# CH340_USB_To_UART.net
KiCad netlist of a schematic drawn in Altium Designer
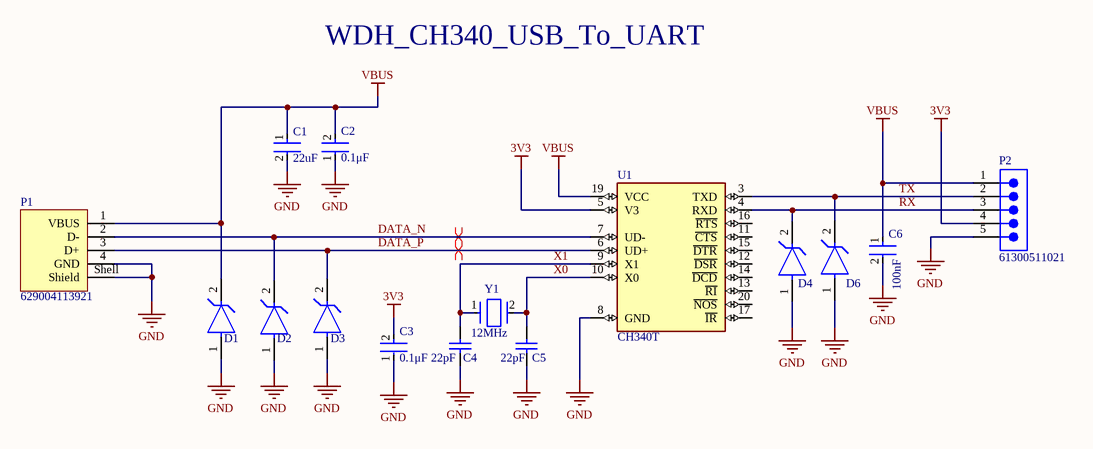
[diagram p0: CH340_USB_To_UART.SchDoc]

(export (version "E")
  (design (tool "Eeschema 10.0.6"))
  (components
    (comp (ref "C1")
      (value "22uF")
      (footprint "FP-CL05A226MQ5N6J8-IPC_C")
      (description "CAP CER 22UF 6.3V X5R 0402")
      (fields
        (field (name "MANUFACTURER PART NUMBER") "CL05A226MQ5N6J8")
        (field (name "MANUFACTURER") "Samsung Electro-Mechanics")
      )
      (libsource (lib "Altium Content Vault") (part "11868f565c42a9108669ba33697ecf6"))
    )
    (comp (ref "C2")
      (value "GRM155R71C104KA88D")
      (footprint "FP-GRM15-MFG")
      (description "CAP CER 0.1UF 16V X7R 0402")
      (fields
        (field (name "TOLERANCE") "10%")
        (field (name "OCTOPART") "https://octopart.com/grm155r71c104ka88d-murata-196880")
        (field (name "CAPACITANCE") "0.1μF")
      )
      (libsource (lib "Altium Content Vault") (part "236180d848d6139a670b325ea6854c9"))
    )
    (comp (ref "C3")
      (value "GRM155R71C104KA88D")
      (footprint "FP-GRM15-MFG")
      (description "CAP CER 0.1UF 16V X7R 0402")
      (fields
        (field (name "TOLERANCE") "10%")
        (field (name "OCTOPART") "https://octopart.com/grm155r71c104ka88d-murata-196880")
        (field (name "CAPACITANCE") "0.1μF")
      )
      (libsource (lib "Altium Content Vault") (part "236180d848d6139a670b325ea6854c9"))
    )
    (comp (ref "C4")
      (value "0402ZK220GBSTR..")
      (footprint "CAPC1006X50X20ML10T10")
      (fields (field (name "MANUFACTURER") "AVX Interconnect / Elco") (field (name "CAPACTANCE") "22pF"))
      (libsource (lib "Altium Content Vault") (part "CAP"))
    )
    (comp (ref "C5")
      (value "0402ZK220GBSTR..")
      (footprint "CAPC1006X50X20ML10T10")
      (fields (field (name "MANUFACTURER") "AVX Interconnect / Elco") (field (name "CAPACTANCE") "22pF"))
      (libsource (lib "Altium Content Vault") (part "CAP"))
    )
    (comp (ref "C6")
      (value "C1005X7R1C104K050BC")
      (footprint "FP-C1005-050-0_05-MFG")
      (description "Multilayer Ceramic Capacitors 100nF ±10% 16V X7R SMD 0402")
      (fields
        (field (name "VOLTAGE") "16V")
        (field (name "CAPACITANCE") "100nF")
        (field (name "TOLERANCE") "10%")
      )
      (libsource (lib "Altium Content Vault") (part "b4654b650e69147ec39a6b967a45e02"))
    )
    (comp (ref "D1")
      (value "UCLAMP3601P.TNT")
      (footprint "FP-SLP1006P2-MFG")
      (description "TVS DIODE 33VWM 60VC SLP1006P2")
      (libsource (lib "Altium Content Vault") (part "3fba79ac723ca0a4e69928609483429"))
    )
    (comp (ref "D2")
      (value "UCLAMP3601P.TNT")
      (footprint "FP-SLP1006P2-MFG")
      (description "TVS DIODE 33VWM 60VC SLP1006P2")
      (libsource (lib "Altium Content Vault") (part "3fba79ac723ca0a4e69928609483429"))
    )
    (comp (ref "D3")
      (value "UCLAMP3601P.TNT")
      (footprint "FP-SLP1006P2-MFG")
      (description "TVS DIODE 33VWM 60VC SLP1006P2")
      (libsource (lib "Altium Content Vault") (part "3fba79ac723ca0a4e69928609483429"))
    )
    (comp (ref "D4")
      (value "UCLAMP3601P.TNT")
      (footprint "FP-SLP1006P2-MFG")
      (description "TVS DIODE 33VWM 60VC SLP1006P2")
      (libsource (lib "Altium Content Vault") (part "3fba79ac723ca0a4e69928609483429"))
    )
    (comp (ref "D6")
      (value "UCLAMP3601P.TNT")
      (footprint "FP-SLP1006P2-MFG")
      (description "TVS DIODE 33VWM 60VC SLP1006P2")
      (libsource (lib "Altium Content Vault") (part "3fba79ac723ca0a4e69928609483429"))
    )
    (comp (ref "P1")
      (value "629004113921")
      (footprint "629004113921")
      (libsource (lib "Altium Content Vault") (part "USB 2.0_Type A_Plug_1 Port"))
    )
    (comp (ref "P2")
      (value "61300511021")
      (footprint "61300511021")
      (libsource (lib "Altium Content Vault") (part "Header_Male_1R_05P"))
    )
    (comp (ref "U1")
      (value "CH340T")
      (footprint "SSOP20W")
      (description "Interface Development Tools USB - Serial Convert with CH340T")
      (fields (field (name "MF") "wch"))
      (libsource (lib "CH340T") (part "CH340T"))
    )
    (comp (ref "Y1")
      (value "ABM3-12.000MHZ-D2Y-T")
      (footprint "FP-ABM3-MFG")
      (description "Crystal 12MHz ±20ppm 18pF SMD-2 5mm x 3.2mm")
      (fields (field (name "TOLERANCE") "20ppm") (field (name "PARAMETER 1") "12MHz"))
      (libsource (lib "Altium Content Vault") (part "c23a69dc6c9e2f18f2079038eb95dd1"))
    )
  )
  (nets
    (net (code "2") (name "/DATA_N") (class "Default")
      (node (ref "D2") (pin "2") (pinfunction "C_2") (pintype "passive"))
      (node (ref "P1") (pin "2") (pinfunction "D-_2") (pintype "passive"))
      (node (ref "U1") (pin "7") (pinfunction "UD-_7") (pintype "bidirectional"))
    )
    (net (code "3") (name "/DATA_P") (class "Default")
      (node (ref "D3") (pin "2") (pinfunction "C_2") (pintype "passive"))
      (node (ref "P1") (pin "3") (pinfunction "D+_3") (pintype "passive"))
      (node (ref "U1") (pin "6") (pinfunction "UD+_6") (pintype "bidirectional"))
    )
    (net (code "4") (name "/RX") (class "Default")
      (node (ref "D4") (pin "2") (pinfunction "C_2") (pintype "passive"))
      (node (ref "P2") (pin "3") (pinfunction "3_3") (pintype "passive"))
      (node (ref "U1") (pin "4") (pinfunction "RXD_4") (pintype "bidirectional"))
    )
    (net (code "5") (name "/TX") (class "Default")
      (node (ref "D6") (pin "2") (pinfunction "C_2") (pintype "passive"))
      (node (ref "P2") (pin "2") (pinfunction "2_2") (pintype "passive"))
      (node (ref "U1") (pin "3") (pinfunction "TXD_3") (pintype "bidirectional"))
    )
    (net (code "6") (name "/X0") (class "Default")
      (node (ref "C5") (pin "2") (pinfunction "2_2") (pintype "passive"))
      (node (ref "U1") (pin "10") (pinfunction "X0_10") (pintype "bidirectional"))
      (node (ref "Y1") (pin "2") (pinfunction "2_2") (pintype "passive"))
    )
    (net (code "7") (name "/X1") (class "Default")
      (node (ref "C4") (pin "2") (pinfunction "2_2") (pintype "passive"))
      (node (ref "U1") (pin "9") (pinfunction "X1_9") (pintype "bidirectional"))
      (node (ref "Y1") (pin "1") (pinfunction "1_1") (pintype "passive"))
    )
    (net (code "8") (name "3V3") (class "Default")
      (node (ref "C3") (pin "2") (pinfunction "2_2") (pintype "passive"))
      (node (ref "P2") (pin "4") (pinfunction "4_4") (pintype "passive"))
      (node (ref "U1") (pin "5") (pinfunction "V3_5") (pintype "bidirectional"))
    )
    (net (code "9") (name "GND") (class "Default")
      (node (ref "C1") (pin "2") (pinfunction "2_2") (pintype "passive"))
      (node (ref "C2") (pin "1") (pinfunction "1_1") (pintype "passive"))
      (node (ref "C3") (pin "1") (pinfunction "1_1") (pintype "passive"))
      (node (ref "C4") (pin "1") (pinfunction "1_1") (pintype "passive"))
      (node (ref "C5") (pin "1") (pinfunction "1_1") (pintype "passive"))
      (node (ref "C6") (pin "2") (pinfunction "2_2") (pintype "passive"))
      (node (ref "D1") (pin "1") (pinfunction "A_1") (pintype "passive"))
      (node (ref "D2") (pin "1") (pinfunction "A_1") (pintype "passive"))
      (node (ref "D3") (pin "1") (pinfunction "A_1") (pintype "passive"))
      (node (ref "D4") (pin "1") (pinfunction "A_1") (pintype "passive"))
      (node (ref "D6") (pin "1") (pinfunction "A_1") (pintype "passive"))
      (node (ref "P1") (pin "4") (pinfunction "GND_4") (pintype "passive"))
      (node (ref "P1") (pin "Shell") (pinfunction "Shield_Shell") (pintype "passive"))
      (node (ref "P2") (pin "5") (pinfunction "5_5") (pintype "passive"))
      (node (ref "U1") (pin "8") (pinfunction "GND_8") (pintype "bidirectional"))
    )
    (net (code "10") (name "VBUS") (class "Default")
      (node (ref "C1") (pin "1") (pinfunction "1_1") (pintype "passive"))
      (node (ref "C2") (pin "2") (pinfunction "2_2") (pintype "passive"))
      (node (ref "C6") (pin "1") (pinfunction "1_1") (pintype "passive"))
      (node (ref "D1") (pin "2") (pinfunction "C_2") (pintype "passive"))
      (node (ref "P1") (pin "1") (pinfunction "VBUS_1") (pintype "passive"))
      (node (ref "P2") (pin "1") (pinfunction "1_1") (pintype "passive"))
      (node (ref "U1") (pin "19") (pinfunction "VCC_19") (pintype "bidirectional"))
    )
    (net (code "11") (name "unconnected-(U1-~{CTS}-Pad11)") (class "Default")
      (node (ref "U1") (pin "11") (pinfunction "~{CTS}_11") (pintype "bidirectional"))
    )
    (net (code "12") (name "unconnected-(U1-~{DCD}-Pad14)") (class "Default")
      (node (ref "U1") (pin "14") (pinfunction "~{DCD}_14") (pintype "bidirectional"))
    )
    (net (code "13") (name "unconnected-(U1-~{DSR}-Pad12)") (class "Default")
      (node (ref "U1") (pin "12") (pinfunction "~{DSR}_12") (pintype "bidirectional"))
    )
    (net (code "14") (name "unconnected-(U1-~{DTR}-Pad15)") (class "Default")
      (node (ref "U1") (pin "15") (pinfunction "~{DTR}_15") (pintype "bidirectional"))
    )
    (net (code "15") (name "unconnected-(U1-~{IR}-Pad17)") (class "Default")
      (node (ref "U1") (pin "17") (pinfunction "~{IR}_17") (pintype "bidirectional"))
    )
    (net (code "16") (name "unconnected-(U1-~{NOS}-Pad20)") (class "Default")
      (node (ref "U1") (pin "20") (pinfunction "~{NOS}_20") (pintype "bidirectional"))
    )
    (net (code "17") (name "unconnected-(U1-~{RI}-Pad13)") (class "Default")
      (node (ref "U1") (pin "13") (pinfunction "~{RI}_13") (pintype "bidirectional"))
    )
    (net (code "18") (name "unconnected-(U1-~{RTS}-Pad16)") (class "Default")
      (node (ref "U1") (pin "16") (pinfunction "~{RTS}_16") (pintype "bidirectional"))
    )
  )
)
